# gpio8p2.net
KiCad netlist of a schematic drawn in EAGLE
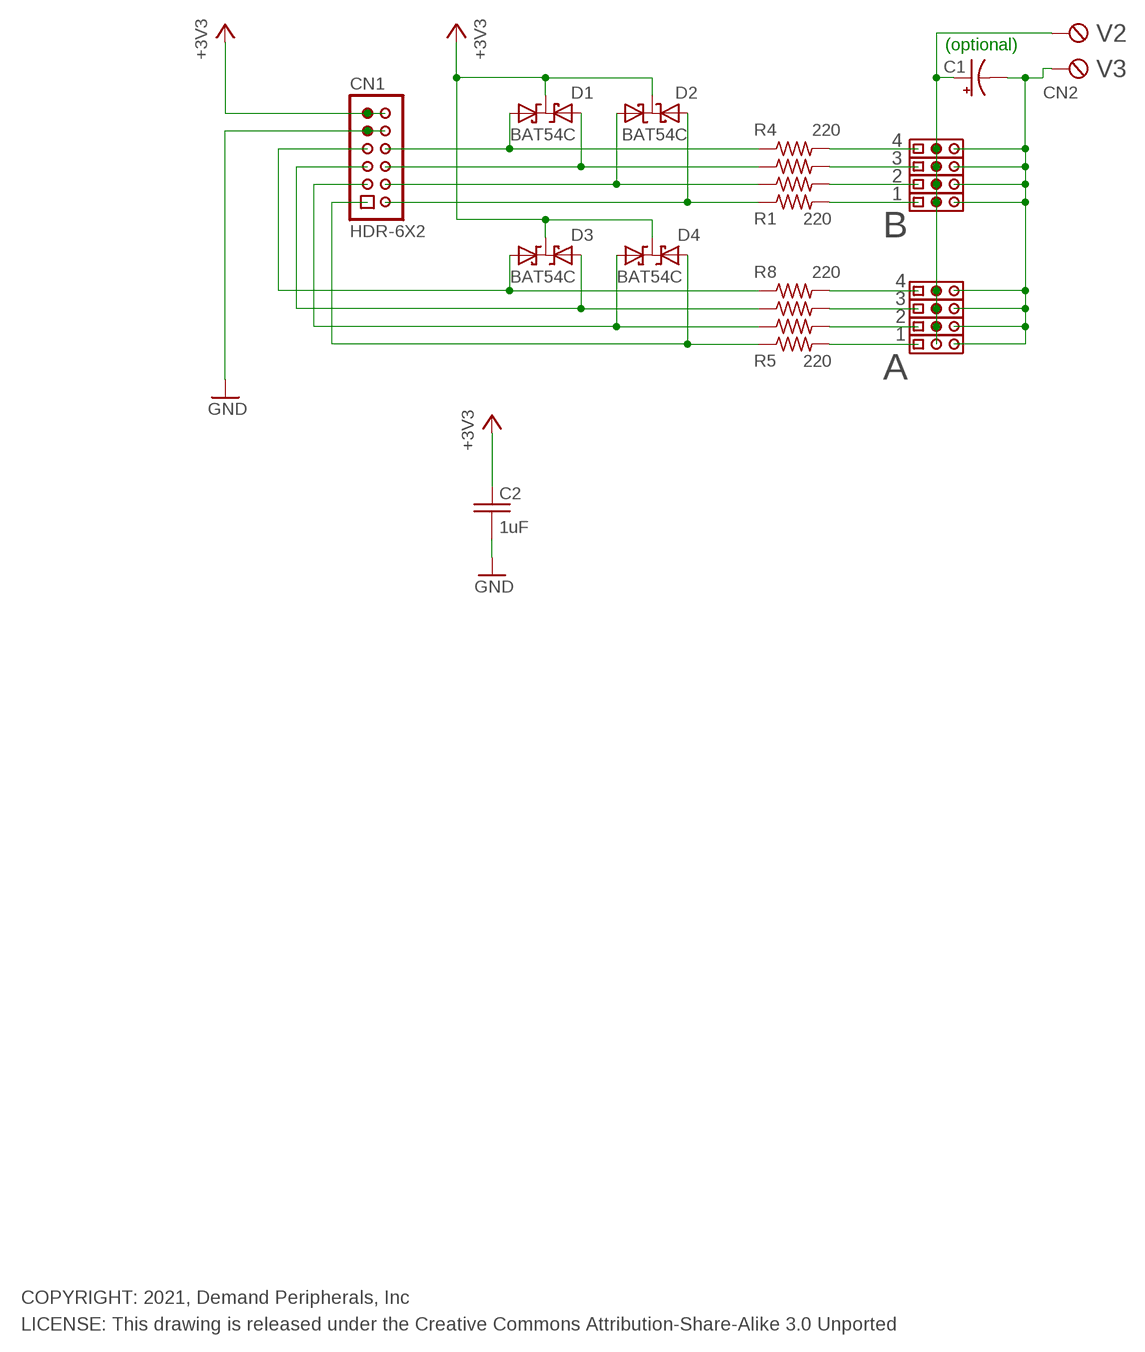
[diagram p0: schematic, sheet 1]

(export (version "E")
  (design (tool "Eeschema 10.0.6"))
  (components
    (comp (ref "C1")
      (value "100uF")
      (footprint "eagle-import:E3.5-8")
      (libsource (lib "eagle-import") (part "C100UF_E3.5-8"))
    )
    (comp (ref "C2")
      (value "1uF")
      (footprint "eagle-import:C0603")
      (libsource (lib "eagle-import") (part "C1.0UF_C0603"))
    )
    (comp (ref "CN1")
      (value "HDR-6X2")
      (footprint "eagle-import:HDR-6X2")
      (libsource (lib "eagle-import") (part "HDR-6X2"))
    )
    (comp (ref "CN2")
      (value "TBLK-5.08-X2")
      (footprint "eagle-import:TBLK-5.08-X2")
      (libsource (lib "eagle-import") (part "TBLK-5.08-X2"))
    )
    (comp (ref "D1")
      (value "BAT54C")
      (footprint "eagle-import:SOT23")
      (libsource (lib "eagle-import") (part "BAT54C"))
    )
    (comp (ref "D2")
      (value "BAT54C")
      (footprint "eagle-import:SOT23")
      (libsource (lib "eagle-import") (part "BAT54C"))
    )
    (comp (ref "D3")
      (value "BAT54C")
      (footprint "eagle-import:SOT23")
      (libsource (lib "eagle-import") (part "BAT54C"))
    )
    (comp (ref "D4")
      (value "BAT54C")
      (footprint "eagle-import:SOT23")
      (libsource (lib "eagle-import") (part "BAT54C"))
    )
    (comp (ref "R1")
      (value "220")
      (footprint "eagle-import:R0603")
      (libsource (lib "eagle-import") (part "R220_R0603"))
    )
    (comp (ref "R2")
      (value "220")
      (footprint "eagle-import:R0603")
      (libsource (lib "eagle-import") (part "R220_R0603"))
    )
    (comp (ref "R3")
      (value "220")
      (footprint "eagle-import:R0603")
      (libsource (lib "eagle-import") (part "R220_R0603"))
    )
    (comp (ref "R4")
      (value "220")
      (footprint "eagle-import:R0603")
      (libsource (lib "eagle-import") (part "R220_R0603"))
    )
    (comp (ref "R5")
      (value "220")
      (footprint "eagle-import:R0603")
      (libsource (lib "eagle-import") (part "R220_R0603"))
    )
    (comp (ref "R6")
      (value "220")
      (footprint "eagle-import:R0603")
      (libsource (lib "eagle-import") (part "R220_R0603"))
    )
    (comp (ref "R7")
      (value "220")
      (footprint "eagle-import:R0603")
      (libsource (lib "eagle-import") (part "R220_R0603"))
    )
    (comp (ref "R8")
      (value "220")
      (footprint "eagle-import:R0603")
      (libsource (lib "eagle-import") (part "R220_R0603"))
    )
    (comp (ref "U$5")
      (value "HDR-3X1")
      (footprint "eagle-import:HDR-3X1")
      (libsource (lib "eagle-import") (part "HDR-3X1"))
    )
    (comp (ref "U$6")
      (value "HDR-3X1")
      (footprint "eagle-import:HDR-3X1")
      (libsource (lib "eagle-import") (part "HDR-3X1"))
    )
    (comp (ref "U$7")
      (value "HDR-3X1")
      (footprint "eagle-import:HDR-3X1")
      (libsource (lib "eagle-import") (part "HDR-3X1"))
    )
    (comp (ref "U$9")
      (value "HDR-3X1")
      (footprint "eagle-import:HDR-3X1")
      (libsource (lib "eagle-import") (part "HDR-3X1"))
    )
    (comp (ref "U$10")
      (value "HDR-3X1")
      (footprint "eagle-import:HDR-3X1")
      (libsource (lib "eagle-import") (part "HDR-3X1"))
    )
    (comp (ref "U$11")
      (value "HDR-3X1")
      (footprint "eagle-import:HDR-3X1")
      (libsource (lib "eagle-import") (part "HDR-3X1"))
    )
    (comp (ref "U$12")
      (value "HDR-3X1")
      (footprint "eagle-import:HDR-3X1")
      (libsource (lib "eagle-import") (part "HDR-3X1"))
    )
    (comp (ref "U$13")
      (value "HDR-3X1")
      (footprint "eagle-import:HDR-3X1")
      (libsource (lib "eagle-import") (part "HDR-3X1"))
    )
  )
  (nets
    (net (code "1") (name "+3V3") (class "Default")
      (node (ref "C2") (pin "1") (pinfunction "1_1") (pintype "passive"))
      (node (ref "CN1") (pin "11") (pinfunction "11_11") (pintype "passive"))
      (node (ref "CN1") (pin "12") (pinfunction "12_12") (pintype "passive"))
      (node (ref "D1") (pin "3") (pinfunction "CC_3") (pintype "passive"))
      (node (ref "D2") (pin "3") (pinfunction "CC_3") (pintype "passive"))
      (node (ref "D3") (pin "3") (pinfunction "CC_3") (pintype "passive"))
      (node (ref "D4") (pin "3") (pinfunction "CC_3") (pintype "passive"))
    )
    (net (code "2") (name "GND") (class "Default")
      (node (ref "C2") (pin "2") (pinfunction "2_2") (pintype "passive"))
      (node (ref "CN1") (pin "10") (pinfunction "10_10") (pintype "passive"))
      (node (ref "CN1") (pin "9") (pinfunction "9_9") (pintype "passive"))
    )
    (net (code "3") (name "Net-(CN2-KL)") (class "Default")
      (node (ref "C1") (pin "-") (pinfunction "-_-") (pintype "passive"))
      (node (ref "CN2") (pin "1") (pinfunction "KL_1") (pintype "passive"))
      (node (ref "U$10") (pin "3") (pinfunction "3_3") (pintype "passive"))
      (node (ref "U$11") (pin "3") (pinfunction "3_3") (pintype "passive"))
      (node (ref "U$12") (pin "3") (pinfunction "3_3") (pintype "passive"))
      (node (ref "U$13") (pin "3") (pinfunction "3_3") (pintype "passive"))
      (node (ref "U$5") (pin "3") (pinfunction "3_3") (pintype "passive"))
      (node (ref "U$6") (pin "3") (pinfunction "3_3") (pintype "passive"))
      (node (ref "U$7") (pin "3") (pinfunction "3_3") (pintype "passive"))
      (node (ref "U$9") (pin "3") (pinfunction "3_3") (pintype "passive"))
    )
    (net (code "4") (name "Net-(CN2-KL1)") (class "Default")
      (node (ref "C1") (pin "+") (pinfunction "+_+") (pintype "passive"))
      (node (ref "CN2") (pin "2") (pinfunction "KL1_2") (pintype "passive"))
      (node (ref "U$10") (pin "2") (pinfunction "2_2") (pintype "passive"))
      (node (ref "U$11") (pin "2") (pinfunction "2_2") (pintype "passive"))
      (node (ref "U$12") (pin "2") (pinfunction "2_2") (pintype "passive"))
      (node (ref "U$13") (pin "2") (pinfunction "2_2") (pintype "passive"))
      (node (ref "U$5") (pin "2") (pinfunction "2_2") (pintype "passive"))
      (node (ref "U$6") (pin "2") (pinfunction "2_2") (pintype "passive"))
      (node (ref "U$7") (pin "2") (pinfunction "2_2") (pintype "passive"))
      (node (ref "U$9") (pin "2") (pinfunction "2_2") (pintype "passive"))
    )
    (net (code "5") (name "Net-(D1-A)") (class "Default")
      (node (ref "CN1") (pin "8") (pinfunction "8_8") (pintype "passive"))
      (node (ref "D1") (pin "2") (pinfunction "A_2") (pintype "passive"))
      (node (ref "R4") (pin "1") (pinfunction "1_1") (pintype "passive"))
    )
    (net (code "6") (name "Net-(D1-A1)") (class "Default")
      (node (ref "CN1") (pin "6") (pinfunction "6_6") (pintype "passive"))
      (node (ref "D1") (pin "1") (pinfunction "A1_1") (pintype "passive"))
      (node (ref "R3") (pin "1") (pinfunction "1_1") (pintype "passive"))
    )
    (net (code "7") (name "Net-(D2-A)") (class "Default")
      (node (ref "CN1") (pin "2") (pinfunction "2_2") (pintype "passive"))
      (node (ref "D2") (pin "2") (pinfunction "A_2") (pintype "passive"))
      (node (ref "R1") (pin "1") (pinfunction "1_1") (pintype "passive"))
    )
    (net (code "8") (name "Net-(D2-A1)") (class "Default")
      (node (ref "CN1") (pin "4") (pinfunction "4_4") (pintype "passive"))
      (node (ref "D2") (pin "1") (pinfunction "A1_1") (pintype "passive"))
      (node (ref "R2") (pin "1") (pinfunction "1_1") (pintype "passive"))
    )
    (net (code "9") (name "Net-(D3-A)") (class "Default")
      (node (ref "CN1") (pin "7") (pinfunction "7_7") (pintype "passive"))
      (node (ref "D3") (pin "2") (pinfunction "A_2") (pintype "passive"))
      (node (ref "R8") (pin "1") (pinfunction "1_1") (pintype "passive"))
    )
    (net (code "10") (name "Net-(D3-A1)") (class "Default")
      (node (ref "CN1") (pin "5") (pinfunction "5_5") (pintype "passive"))
      (node (ref "D3") (pin "1") (pinfunction "A1_1") (pintype "passive"))
      (node (ref "R7") (pin "1") (pinfunction "1_1") (pintype "passive"))
    )
    (net (code "11") (name "Net-(D4-A)") (class "Default")
      (node (ref "CN1") (pin "3") (pinfunction "3_3") (pintype "passive"))
      (node (ref "D4") (pin "2") (pinfunction "A_2") (pintype "passive"))
      (node (ref "R6") (pin "1") (pinfunction "1_1") (pintype "passive"))
    )
    (net (code "12") (name "Net-(D4-A1)") (class "Default")
      (node (ref "CN1") (pin "1") (pinfunction "1_1") (pintype "passive"))
      (node (ref "D4") (pin "1") (pinfunction "A1_1") (pintype "passive"))
      (node (ref "R5") (pin "1") (pinfunction "1_1") (pintype "passive"))
    )
    (net (code "13") (name "Net-(R1-Pad2)") (class "Default")
      (node (ref "R1") (pin "2") (pinfunction "2_2") (pintype "passive"))
      (node (ref "U$9") (pin "1") (pinfunction "1_1") (pintype "passive"))
    )
    (net (code "14") (name "Net-(R2-Pad2)") (class "Default")
      (node (ref "R2") (pin "2") (pinfunction "2_2") (pintype "passive"))
      (node (ref "U$7") (pin "1") (pinfunction "1_1") (pintype "passive"))
    )
    (net (code "15") (name "Net-(R3-Pad2)") (class "Default")
      (node (ref "R3") (pin "2") (pinfunction "2_2") (pintype "passive"))
      (node (ref "U$6") (pin "1") (pinfunction "1_1") (pintype "passive"))
    )
    (net (code "16") (name "Net-(R4-Pad2)") (class "Default")
      (node (ref "R4") (pin "2") (pinfunction "2_2") (pintype "passive"))
      (node (ref "U$5") (pin "1") (pinfunction "1_1") (pintype "passive"))
    )
    (net (code "17") (name "Net-(R5-Pad2)") (class "Default")
      (node (ref "R5") (pin "2") (pinfunction "2_2") (pintype "passive"))
      (node (ref "U$13") (pin "1") (pinfunction "1_1") (pintype "passive"))
    )
    (net (code "18") (name "Net-(R6-Pad2)") (class "Default")
      (node (ref "R6") (pin "2") (pinfunction "2_2") (pintype "passive"))
      (node (ref "U$12") (pin "1") (pinfunction "1_1") (pintype "passive"))
    )
    (net (code "19") (name "Net-(R7-Pad2)") (class "Default")
      (node (ref "R7") (pin "2") (pinfunction "2_2") (pintype "passive"))
      (node (ref "U$11") (pin "1") (pinfunction "1_1") (pintype "passive"))
    )
    (net (code "20") (name "Net-(R8-Pad2)") (class "Default")
      (node (ref "R8") (pin "2") (pinfunction "2_2") (pintype "passive"))
      (node (ref "U$10") (pin "1") (pinfunction "1_1") (pintype "passive"))
    )
  )
)
